# midi_pad.net
KiCad netlist of a schematic drawn in EAGLE
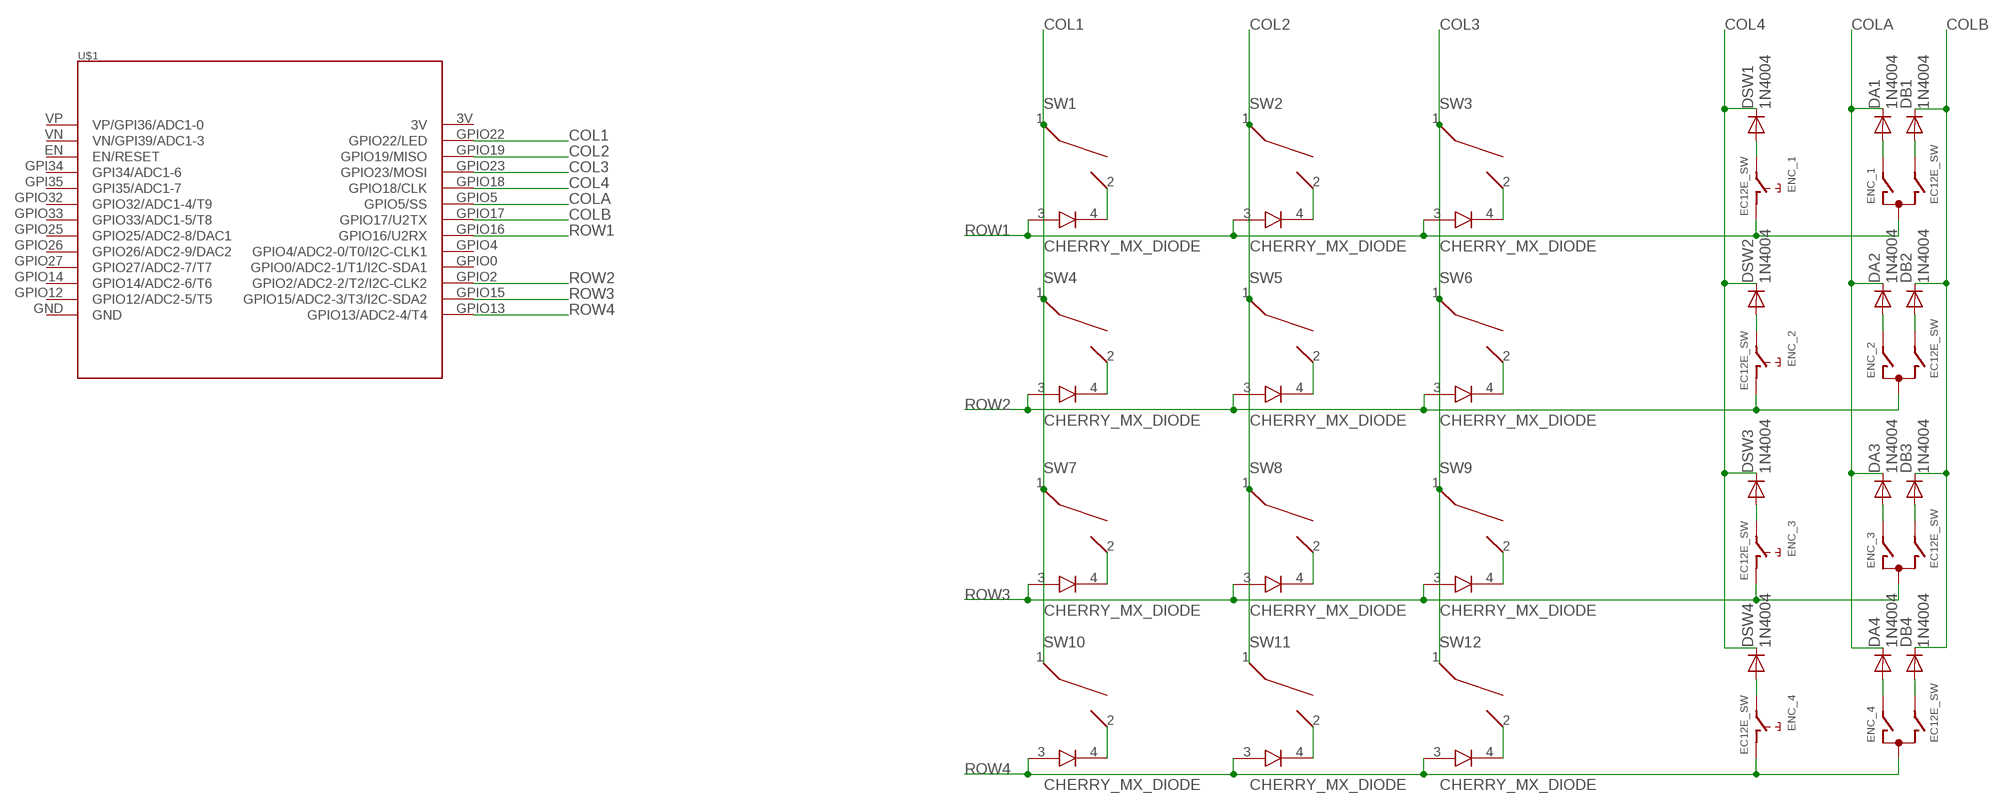
[diagram p0: schematic, sheet 1]

(export (version "E")
  (design (tool "Eeschema 10.0.6"))
  (components
    (comp (ref "DA1")
      (value "1N4004")
      (footprint "eagle-import:DO41-10")
      (libsource (lib "eagle-import") (part "1N4004"))
    )
    (comp (ref "DA2")
      (value "1N4004")
      (footprint "eagle-import:DO41-10")
      (libsource (lib "eagle-import") (part "1N4004"))
    )
    (comp (ref "DA3")
      (value "1N4004")
      (footprint "eagle-import:DO41-10")
      (libsource (lib "eagle-import") (part "1N4004"))
    )
    (comp (ref "DA4")
      (value "1N4004")
      (footprint "eagle-import:DO41-10")
      (libsource (lib "eagle-import") (part "1N4004"))
    )
    (comp (ref "DB1")
      (value "1N4004")
      (footprint "eagle-import:DO41-10")
      (libsource (lib "eagle-import") (part "1N4004"))
    )
    (comp (ref "DB2")
      (value "1N4004")
      (footprint "eagle-import:DO41-10")
      (libsource (lib "eagle-import") (part "1N4004"))
    )
    (comp (ref "DB3")
      (value "1N4004")
      (footprint "eagle-import:DO41-10")
      (libsource (lib "eagle-import") (part "1N4004"))
    )
    (comp (ref "DB4")
      (value "1N4004")
      (footprint "eagle-import:DO41-10")
      (libsource (lib "eagle-import") (part "1N4004"))
    )
    (comp (ref "DSW1")
      (value "1N4004")
      (footprint "eagle-import:DO41-10")
      (libsource (lib "eagle-import") (part "1N4004"))
    )
    (comp (ref "DSW2")
      (value "1N4004")
      (footprint "eagle-import:DO41-10")
      (libsource (lib "eagle-import") (part "1N4004"))
    )
    (comp (ref "DSW3")
      (value "1N4004")
      (footprint "eagle-import:DO41-10")
      (libsource (lib "eagle-import") (part "1N4004"))
    )
    (comp (ref "DSW4")
      (value "1N4004")
      (footprint "eagle-import:DO41-10")
      (libsource (lib "eagle-import") (part "1N4004"))
    )
    (comp (ref "ENC_1")
      (value "EC12E_SW")
      (footprint "eagle-import:ALPS_EC12E_SW")
      (fields (field (name "MPN") "EC12E2424407"))
      (libsource (lib "eagle-import") (part "EC12E_SW"))
    )
    (comp (ref "ENC_2")
      (value "EC12E_SW")
      (footprint "eagle-import:ALPS_EC12E_SW")
      (fields (field (name "MPN") "EC12E2424407"))
      (libsource (lib "eagle-import") (part "EC12E_SW"))
    )
    (comp (ref "ENC_3")
      (value "EC12E_SW")
      (footprint "eagle-import:ALPS_EC12E_SW")
      (fields (field (name "MPN") "EC12E2424407"))
      (libsource (lib "eagle-import") (part "EC12E_SW"))
    )
    (comp (ref "ENC_4")
      (value "EC12E_SW")
      (footprint "eagle-import:ALPS_EC12E_SW")
      (fields (field (name "MPN") "EC12E2424407"))
      (libsource (lib "eagle-import") (part "EC12E_SW"))
    )
    (comp (ref "SW1")
      (value "CHERRY_MX_DIODE")
      (footprint "eagle-import:MX1A-XX[D_J]N")
      (libsource (lib "eagle-import") (part "CHERRY_MX_DIODE"))
    )
    (comp (ref "SW2")
      (value "CHERRY_MX_DIODE")
      (footprint "eagle-import:MX1A-XX[D_J]N")
      (libsource (lib "eagle-import") (part "CHERRY_MX_DIODE"))
    )
    (comp (ref "SW3")
      (value "CHERRY_MX_DIODE")
      (footprint "eagle-import:MX1A-XX[D_J]N")
      (libsource (lib "eagle-import") (part "CHERRY_MX_DIODE"))
    )
    (comp (ref "SW4")
      (value "CHERRY_MX_DIODE")
      (footprint "eagle-import:MX1A-XX[D_J]N")
      (libsource (lib "eagle-import") (part "CHERRY_MX_DIODE"))
    )
    (comp (ref "SW5")
      (value "CHERRY_MX_DIODE")
      (footprint "eagle-import:MX1A-XX[D_J]N")
      (libsource (lib "eagle-import") (part "CHERRY_MX_DIODE"))
    )
    (comp (ref "SW6")
      (value "CHERRY_MX_DIODE")
      (footprint "eagle-import:MX1A-XX[D_J]N")
      (libsource (lib "eagle-import") (part "CHERRY_MX_DIODE"))
    )
    (comp (ref "SW7")
      (value "CHERRY_MX_DIODE")
      (footprint "eagle-import:MX1A-XX[D_J]N")
      (libsource (lib "eagle-import") (part "CHERRY_MX_DIODE"))
    )
    (comp (ref "SW8")
      (value "CHERRY_MX_DIODE")
      (footprint "eagle-import:MX1A-XX[D_J]N")
      (libsource (lib "eagle-import") (part "CHERRY_MX_DIODE"))
    )
    (comp (ref "SW9")
      (value "CHERRY_MX_DIODE")
      (footprint "eagle-import:MX1A-XX[D_J]N")
      (libsource (lib "eagle-import") (part "CHERRY_MX_DIODE"))
    )
    (comp (ref "SW10")
      (value "CHERRY_MX_DIODE")
      (footprint "eagle-import:MX1A-XX[D_J]N")
      (libsource (lib "eagle-import") (part "CHERRY_MX_DIODE"))
    )
    (comp (ref "SW11")
      (value "CHERRY_MX_DIODE")
      (footprint "eagle-import:MX1A-XX[D_J]N")
      (libsource (lib "eagle-import") (part "CHERRY_MX_DIODE"))
    )
    (comp (ref "SW12")
      (value "CHERRY_MX_DIODE")
      (footprint "eagle-import:MX1A-XX[D_J]N")
      (libsource (lib "eagle-import") (part "CHERRY_MX_DIODE"))
    )
    (comp (ref "U$1")
      (value "LOLIN32_LITE")
      (footprint "eagle-import:LOLIN32_LITE")
      (libsource (lib "eagle-import") (part "LOLIN32_LITE"))
    )
  )
  (nets
    (net (code "1") (name "/COL1") (class "Default")
      (node (ref "SW1") (pin "1") (pinfunction "1_1") (pintype "passive"))
      (node (ref "SW10") (pin "1") (pinfunction "1_1") (pintype "passive"))
      (node (ref "SW4") (pin "1") (pinfunction "1_1") (pintype "passive"))
      (node (ref "SW7") (pin "1") (pinfunction "1_1") (pintype "passive"))
      (node (ref "U$1") (pin "GPIO22") (pinfunction "GPIO22/LED_GPIO22") (pintype "bidirectional"))
    )
    (net (code "2") (name "/COL2") (class "Default")
      (node (ref "SW11") (pin "1") (pinfunction "1_1") (pintype "passive"))
      (node (ref "SW2") (pin "1") (pinfunction "1_1") (pintype "passive"))
      (node (ref "SW5") (pin "1") (pinfunction "1_1") (pintype "passive"))
      (node (ref "SW8") (pin "1") (pinfunction "1_1") (pintype "passive"))
      (node (ref "U$1") (pin "GPIO19") (pinfunction "GPIO19/MISO_GPIO19") (pintype "bidirectional"))
    )
    (net (code "3") (name "/COL3") (class "Default")
      (node (ref "SW12") (pin "1") (pinfunction "1_1") (pintype "passive"))
      (node (ref "SW3") (pin "1") (pinfunction "1_1") (pintype "passive"))
      (node (ref "SW6") (pin "1") (pinfunction "1_1") (pintype "passive"))
      (node (ref "SW9") (pin "1") (pinfunction "1_1") (pintype "passive"))
      (node (ref "U$1") (pin "GPIO23") (pinfunction "GPIO23/MOSI_GPIO23") (pintype "bidirectional"))
    )
    (net (code "4") (name "/COL4") (class "Default")
      (node (ref "DSW1") (pin "C") (pinfunction "C_C") (pintype "passive"))
      (node (ref "DSW2") (pin "C") (pinfunction "C_C") (pintype "passive"))
      (node (ref "DSW3") (pin "C") (pinfunction "C_C") (pintype "passive"))
      (node (ref "DSW4") (pin "C") (pinfunction "C_C") (pintype "passive"))
      (node (ref "U$1") (pin "GPIO18") (pinfunction "GPIO18/CLK_GPIO18") (pintype "bidirectional"))
    )
    (net (code "5") (name "/COLA") (class "Default")
      (node (ref "DA1") (pin "C") (pinfunction "C_C") (pintype "passive"))
      (node (ref "DA2") (pin "C") (pinfunction "C_C") (pintype "passive"))
      (node (ref "DA3") (pin "C") (pinfunction "C_C") (pintype "passive"))
      (node (ref "DA4") (pin "C") (pinfunction "C_C") (pintype "passive"))
      (node (ref "U$1") (pin "GPIO5") (pinfunction "GPIO5/SS_GPIO5") (pintype "bidirectional"))
    )
    (net (code "6") (name "/COLB") (class "Default")
      (node (ref "DB1") (pin "C") (pinfunction "C_C") (pintype "passive"))
      (node (ref "DB2") (pin "C") (pinfunction "C_C") (pintype "passive"))
      (node (ref "DB3") (pin "C") (pinfunction "C_C") (pintype "passive"))
      (node (ref "DB4") (pin "C") (pinfunction "C_C") (pintype "passive"))
      (node (ref "U$1") (pin "GPIO17") (pinfunction "GPIO17/U2TX_GPIO17") (pintype "bidirectional"))
    )
    (net (code "7") (name "/ROW1") (class "Default")
      (node (ref "ENC_1") (pin "C") (pinfunction "C_C") (pintype "passive"))
      (node (ref "ENC_1") (pin "D") (pinfunction "1_D") (pintype "passive"))
      (node (ref "SW1") (pin "3") (pinfunction "3_3") (pintype "passive"))
      (node (ref "SW2") (pin "3") (pinfunction "3_3") (pintype "passive"))
      (node (ref "SW3") (pin "3") (pinfunction "3_3") (pintype "passive"))
      (node (ref "U$1") (pin "GPIO16") (pinfunction "GPIO16/U2RX_GPIO16") (pintype "bidirectional"))
    )
    (net (code "8") (name "/ROW2") (class "Default")
      (node (ref "ENC_2") (pin "C") (pinfunction "C_C") (pintype "passive"))
      (node (ref "ENC_2") (pin "D") (pinfunction "1_D") (pintype "passive"))
      (node (ref "SW4") (pin "3") (pinfunction "3_3") (pintype "passive"))
      (node (ref "SW5") (pin "3") (pinfunction "3_3") (pintype "passive"))
      (node (ref "SW6") (pin "3") (pinfunction "3_3") (pintype "passive"))
      (node (ref "U$1") (pin "GPIO2") (pinfunction "GPIO2/ADC2-2/T2/I2C-CLK2_GPIO2") (pintype "bidirectional"))
    )
    (net (code "9") (name "/ROW3") (class "Default")
      (node (ref "ENC_3") (pin "C") (pinfunction "C_C") (pintype "passive"))
      (node (ref "ENC_3") (pin "D") (pinfunction "1_D") (pintype "passive"))
      (node (ref "SW7") (pin "3") (pinfunction "3_3") (pintype "passive"))
      (node (ref "SW8") (pin "3") (pinfunction "3_3") (pintype "passive"))
      (node (ref "SW9") (pin "3") (pinfunction "3_3") (pintype "passive"))
      (node (ref "U$1") (pin "GPIO15") (pinfunction "GPIO15/ADC2-3/T3/I2C-SDA2_GPIO15") (pintype "bidirectional"))
    )
    (net (code "10") (name "/ROW4") (class "Default")
      (node (ref "ENC_4") (pin "C") (pinfunction "C_C") (pintype "passive"))
      (node (ref "ENC_4") (pin "D") (pinfunction "1_D") (pintype "passive"))
      (node (ref "SW10") (pin "3") (pinfunction "3_3") (pintype "passive"))
      (node (ref "SW11") (pin "3") (pinfunction "3_3") (pintype "passive"))
      (node (ref "SW12") (pin "3") (pinfunction "3_3") (pintype "passive"))
      (node (ref "U$1") (pin "GPIO13") (pinfunction "GPIO13/ADC2-4/T4_GPIO13") (pintype "bidirectional"))
    )
    (net (code "11") (name "Net-(DA1-PadA)") (class "Default")
      (node (ref "DA1") (pin "A") (pinfunction "A_A") (pintype "passive"))
      (node (ref "ENC_1") (pin "A") (pinfunction "A_A") (pintype "passive"))
    )
    (net (code "12") (name "Net-(DA2-PadA)") (class "Default")
      (node (ref "DA2") (pin "A") (pinfunction "A_A") (pintype "passive"))
      (node (ref "ENC_2") (pin "A") (pinfunction "A_A") (pintype "passive"))
    )
    (net (code "13") (name "Net-(DA3-PadA)") (class "Default")
      (node (ref "DA3") (pin "A") (pinfunction "A_A") (pintype "passive"))
      (node (ref "ENC_3") (pin "A") (pinfunction "A_A") (pintype "passive"))
    )
    (net (code "14") (name "Net-(DA4-PadA)") (class "Default")
      (node (ref "DA4") (pin "A") (pinfunction "A_A") (pintype "passive"))
      (node (ref "ENC_4") (pin "A") (pinfunction "A_A") (pintype "passive"))
    )
    (net (code "15") (name "Net-(DB1-PadA)") (class "Default")
      (node (ref "DB1") (pin "A") (pinfunction "A_A") (pintype "passive"))
      (node (ref "ENC_1") (pin "B") (pinfunction "B_B") (pintype "passive"))
    )
    (net (code "16") (name "Net-(DB2-PadA)") (class "Default")
      (node (ref "DB2") (pin "A") (pinfunction "A_A") (pintype "passive"))
      (node (ref "ENC_2") (pin "B") (pinfunction "B_B") (pintype "passive"))
    )
    (net (code "17") (name "Net-(DB3-PadA)") (class "Default")
      (node (ref "DB3") (pin "A") (pinfunction "A_A") (pintype "passive"))
      (node (ref "ENC_3") (pin "B") (pinfunction "B_B") (pintype "passive"))
    )
    (net (code "18") (name "Net-(DB4-PadA)") (class "Default")
      (node (ref "DB4") (pin "A") (pinfunction "A_A") (pintype "passive"))
      (node (ref "ENC_4") (pin "B") (pinfunction "B_B") (pintype "passive"))
    )
    (net (code "19") (name "Net-(ENC_1B-2)") (class "Default")
      (node (ref "DSW1") (pin "A") (pinfunction "A_A") (pintype "passive"))
      (node (ref "ENC_1") (pin "E") (pinfunction "2_E") (pintype "passive"))
    )
    (net (code "20") (name "Net-(ENC_2B-2)") (class "Default")
      (node (ref "DSW2") (pin "A") (pinfunction "A_A") (pintype "passive"))
      (node (ref "ENC_2") (pin "E") (pinfunction "2_E") (pintype "passive"))
    )
    (net (code "21") (name "Net-(ENC_3B-2)") (class "Default")
      (node (ref "DSW3") (pin "A") (pinfunction "A_A") (pintype "passive"))
      (node (ref "ENC_3") (pin "E") (pinfunction "2_E") (pintype "passive"))
    )
    (net (code "22") (name "Net-(ENC_4B-2)") (class "Default")
      (node (ref "DSW4") (pin "A") (pinfunction "A_A") (pintype "passive"))
      (node (ref "ENC_4") (pin "E") (pinfunction "2_E") (pintype "passive"))
    )
    (net (code "23") (name "Net-(SW1-Pad2)") (class "Default")
      (node (ref "SW1") (pin "2") (pinfunction "2_2") (pintype "passive"))
      (node (ref "SW1") (pin "4") (pinfunction "4_4") (pintype "passive"))
    )
    (net (code "24") (name "Net-(SW2-Pad2)") (class "Default")
      (node (ref "SW2") (pin "2") (pinfunction "2_2") (pintype "passive"))
      (node (ref "SW2") (pin "4") (pinfunction "4_4") (pintype "passive"))
    )
    (net (code "25") (name "Net-(SW3-Pad2)") (class "Default")
      (node (ref "SW3") (pin "2") (pinfunction "2_2") (pintype "passive"))
      (node (ref "SW3") (pin "4") (pinfunction "4_4") (pintype "passive"))
    )
    (net (code "26") (name "Net-(SW4-Pad2)") (class "Default")
      (node (ref "SW4") (pin "2") (pinfunction "2_2") (pintype "passive"))
      (node (ref "SW4") (pin "4") (pinfunction "4_4") (pintype "passive"))
    )
    (net (code "27") (name "Net-(SW5-Pad2)") (class "Default")
      (node (ref "SW5") (pin "2") (pinfunction "2_2") (pintype "passive"))
      (node (ref "SW5") (pin "4") (pinfunction "4_4") (pintype "passive"))
    )
    (net (code "28") (name "Net-(SW6-Pad2)") (class "Default")
      (node (ref "SW6") (pin "2") (pinfunction "2_2") (pintype "passive"))
      (node (ref "SW6") (pin "4") (pinfunction "4_4") (pintype "passive"))
    )
    (net (code "29") (name "Net-(SW7-Pad2)") (class "Default")
      (node (ref "SW7") (pin "2") (pinfunction "2_2") (pintype "passive"))
      (node (ref "SW7") (pin "4") (pinfunction "4_4") (pintype "passive"))
    )
    (net (code "30") (name "Net-(SW8-Pad2)") (class "Default")
      (node (ref "SW8") (pin "2") (pinfunction "2_2") (pintype "passive"))
      (node (ref "SW8") (pin "4") (pinfunction "4_4") (pintype "passive"))
    )
    (net (code "31") (name "Net-(SW9-Pad2)") (class "Default")
      (node (ref "SW9") (pin "2") (pinfunction "2_2") (pintype "passive"))
      (node (ref "SW9") (pin "4") (pinfunction "4_4") (pintype "passive"))
    )
    (net (code "32") (name "Net-(SW10-Pad2)") (class "Default")
      (node (ref "SW10") (pin "2") (pinfunction "2_2") (pintype "passive"))
      (node (ref "SW10") (pin "4") (pinfunction "4_4") (pintype "passive"))
    )
    (net (code "33") (name "Net-(SW11-Pad2)") (class "Default")
      (node (ref "SW11") (pin "2") (pinfunction "2_2") (pintype "passive"))
      (node (ref "SW11") (pin "4") (pinfunction "4_4") (pintype "passive"))
    )
    (net (code "34") (name "Net-(SW12-Pad2)") (class "Default")
      (node (ref "SW12") (pin "2") (pinfunction "2_2") (pintype "passive"))
      (node (ref "SW12") (pin "4") (pinfunction "4_4") (pintype "passive"))
    )
    (net (code "35") (name "unconnected-(U$1-EN{slash}RESET-PadEN)") (class "Default")
      (node (ref "U$1") (pin "EN") (pinfunction "EN/RESET_EN") (pintype "bidirectional"))
    )
    (net (code "36") (name "unconnected-(U$1-GPI34{slash}ADC1-6-PadGPI34)") (class "Default")
      (node (ref "U$1") (pin "GPI34") (pinfunction "GPI34/ADC1-6_GPI34") (pintype "bidirectional"))
    )
    (net (code "37") (name "unconnected-(U$1-GPI35{slash}ADC1-7-PadGPI35)") (class "Default")
      (node (ref "U$1") (pin "GPI35") (pinfunction "GPI35/ADC1-7_GPI35") (pintype "bidirectional"))
    )
    (net (code "38") (name "unconnected-(U$1-GPIO0{slash}ADC2-1{slash}T1{slash}I2C-SDA1-PadGPIO0)") (class "Default")
      (node (ref "U$1") (pin "GPIO0") (pinfunction "GPIO0/ADC2-1/T1/I2C-SDA1_GPIO0") (pintype "bidirectional"))
    )
    (net (code "39") (name "unconnected-(U$1-GPIO4{slash}ADC2-0{slash}T0{slash}I2C-CLK1-PadGPIO4)") (class "Default")
      (node (ref "U$1") (pin "GPIO4") (pinfunction "GPIO4/ADC2-0/T0/I2C-CLK1_GPIO4") (pintype "bidirectional"))
    )
    (net (code "40") (name "unconnected-(U$1-GPIO12{slash}ADC2-5{slash}T5-PadGPIO12)") (class "Default")
      (node (ref "U$1") (pin "GPIO12") (pinfunction "GPIO12/ADC2-5/T5_GPIO12") (pintype "bidirectional"))
    )
    (net (code "41") (name "unconnected-(U$1-GPIO14{slash}ADC2-6{slash}T6-PadGPIO14)") (class "Default")
      (node (ref "U$1") (pin "GPIO14") (pinfunction "GPIO14/ADC2-6/T6_GPIO14") (pintype "bidirectional"))
    )
    (net (code "42") (name "unconnected-(U$1-GPIO25{slash}ADC2-8{slash}DAC1-PadGPIO25)") (class "Default")
      (node (ref "U$1") (pin "GPIO25") (pinfunction "GPIO25/ADC2-8/DAC1_GPIO25") (pintype "bidirectional"))
    )
    (net (code "43") (name "unconnected-(U$1-GPIO26{slash}ADC2-9{slash}DAC2-PadGPIO26)") (class "Default")
      (node (ref "U$1") (pin "GPIO26") (pinfunction "GPIO26/ADC2-9/DAC2_GPIO26") (pintype "bidirectional"))
    )
    (net (code "44") (name "unconnected-(U$1-GPIO27{slash}ADC2-7{slash}T7-PadGPIO27)") (class "Default")
      (node (ref "U$1") (pin "GPIO27") (pinfunction "GPIO27/ADC2-7/T7_GPIO27") (pintype "bidirectional"))
    )
    (net (code "45") (name "unconnected-(U$1-GPIO32{slash}ADC1-4{slash}T9-PadGPIO32)") (class "Default")
      (node (ref "U$1") (pin "GPIO32") (pinfunction "GPIO32/ADC1-4/T9_GPIO32") (pintype "bidirectional"))
    )
    (net (code "46") (name "unconnected-(U$1-GPIO33{slash}ADC1-5{slash}T8-PadGPIO33)") (class "Default")
      (node (ref "U$1") (pin "GPIO33") (pinfunction "GPIO33/ADC1-5/T8_GPIO33") (pintype "bidirectional"))
    )
    (net (code "47") (name "unconnected-(U$1-Pad3V)") (class "Default")
      (node (ref "U$1") (pin "3V") (pinfunction "3V_3V") (pintype "bidirectional"))
    )
    (net (code "48") (name "unconnected-(U$1-PadGND)") (class "Default")
      (node (ref "U$1") (pin "GND") (pinfunction "GND_GND") (pintype "bidirectional"))
    )
    (net (code "49") (name "unconnected-(U$1-VN{slash}GPI39{slash}ADC1-3-PadVN)") (class "Default")
      (node (ref "U$1") (pin "VN") (pinfunction "VN/GPI39/ADC1-3_VN") (pintype "bidirectional"))
    )
    (net (code "50") (name "unconnected-(U$1-VP{slash}GPI36{slash}ADC1-0-PadVP)") (class "Default")
      (node (ref "U$1") (pin "VP") (pinfunction "VP/GPI36/ADC1-0_VP") (pintype "bidirectional"))
    )
  )
)
